# Schematic.net
KiCad netlist of a schematic drawn in EAGLE
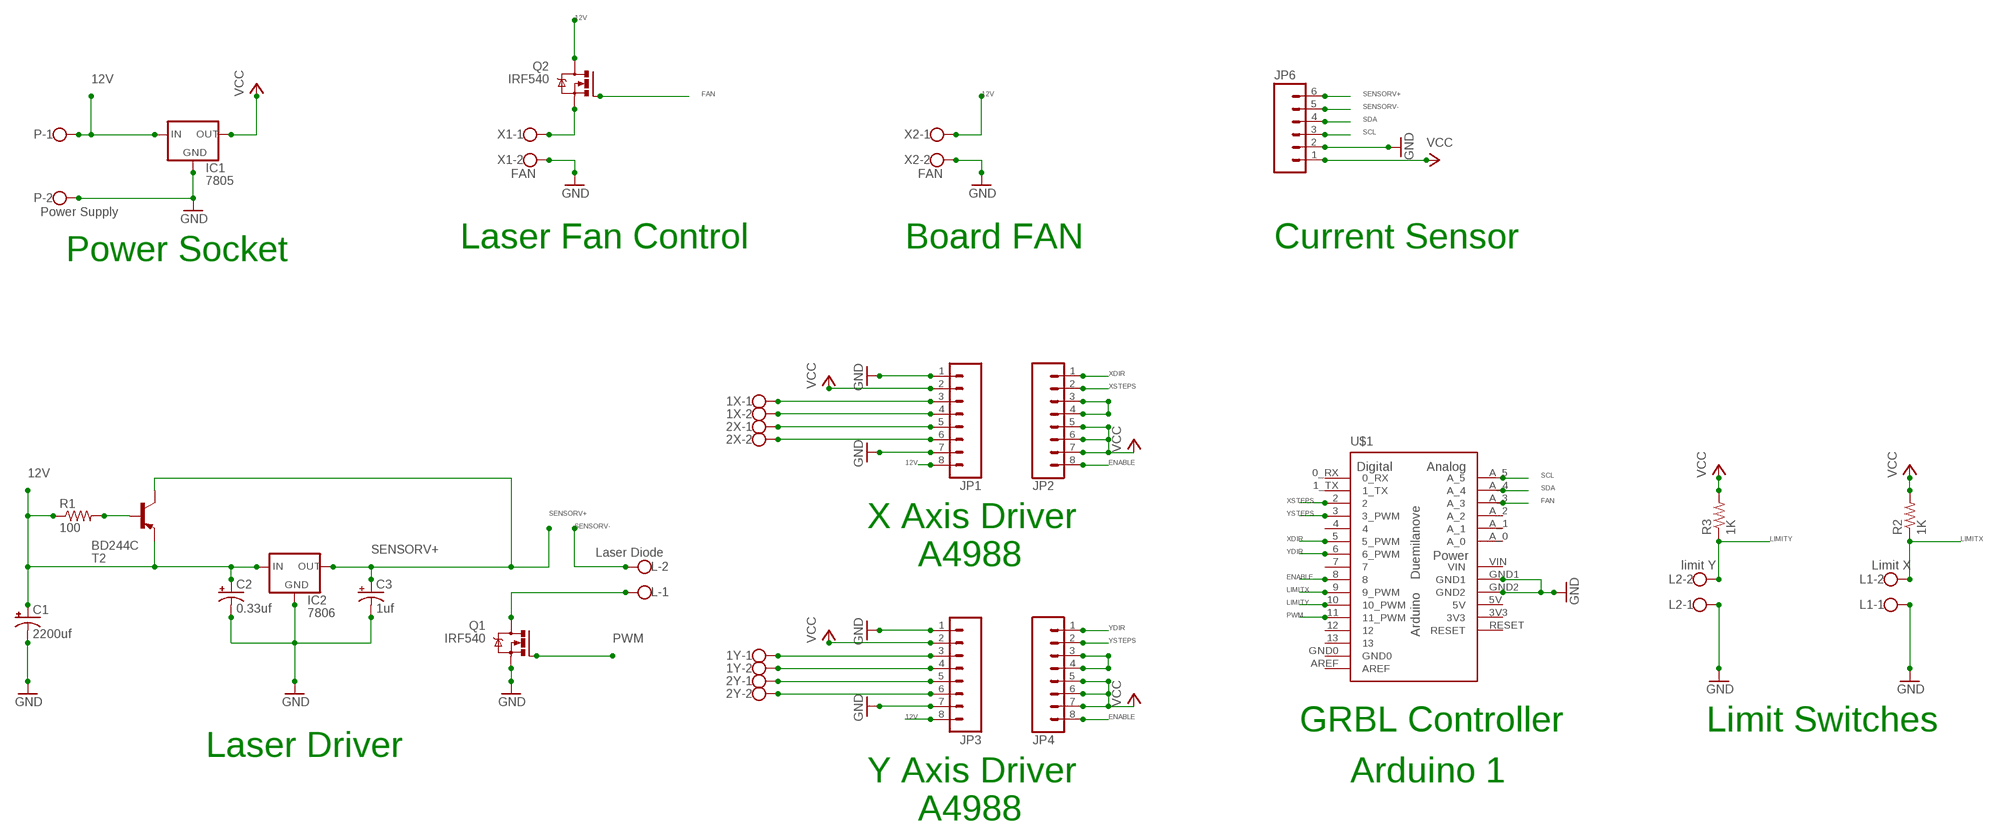
[diagram p0: schematic, sheet 1]

(export (version "E")
  (design (tool "Eeschema 10.0.6"))
  (components
    (comp (ref "1X")
      (value "W237-102")
      (footprint "eagle-import:W237-102")
      (fields (field (name "MPN") "237-102"))
      (libsource (lib "eagle-import") (part "W237-102"))
    )
    (comp (ref "1Y")
      (value "W237-102")
      (footprint "eagle-import:W237-102")
      (fields (field (name "MPN") "237-102"))
      (libsource (lib "eagle-import") (part "W237-102"))
    )
    (comp (ref "2X")
      (value "W237-102")
      (footprint "eagle-import:W237-102")
      (fields (field (name "MPN") "237-102"))
      (libsource (lib "eagle-import") (part "W237-102"))
    )
    (comp (ref "2Y")
      (value "W237-102")
      (footprint "eagle-import:W237-102")
      (fields (field (name "MPN") "237-102"))
      (libsource (lib "eagle-import") (part "W237-102"))
    )
    (comp (ref "C1")
      (value "2200uf")
      (footprint "eagle-import:CPOL-RADIAL-1000UF-25V")
      (libsource (lib "eagle-import") (part "CAP_POLPTH4"))
    )
    (comp (ref "C2")
      (value "0.33uf")
      (footprint "eagle-import:CPOL-RADIAL-10UF-25V")
      (libsource (lib "eagle-import") (part "CAP_POLPTH2"))
    )
    (comp (ref "C3")
      (value "1uf")
      (footprint "eagle-import:CPOL-RADIAL-10UF-25V")
      (libsource (lib "eagle-import") (part "CAP_POLPTH2"))
    )
    (comp (ref "IC1")
      (value "7805")
      (footprint "eagle-import:TO220-IGO")
      (libsource (lib "eagle-import") (part "V_REG_78XXSINK"))
    )
    (comp (ref "IC2")
      (value "7806")
      (footprint "eagle-import:TO220-IGO")
      (libsource (lib "eagle-import") (part "V_REG_78XXSINK"))
    )
    (comp (ref "JP1")
      (value "M08")
      (footprint "eagle-import:1X08")
      (libsource (lib "eagle-import") (part "M08"))
    )
    (comp (ref "JP2")
      (value "M08")
      (footprint "eagle-import:1X08")
      (libsource (lib "eagle-import") (part "M08"))
    )
    (comp (ref "JP3")
      (value "M08")
      (footprint "eagle-import:1X08")
      (libsource (lib "eagle-import") (part "M08"))
    )
    (comp (ref "JP4")
      (value "M08")
      (footprint "eagle-import:1X08")
      (libsource (lib "eagle-import") (part "M08"))
    )
    (comp (ref "JP6")
      (value "M06LONGPADS")
      (footprint "eagle-import:1X06_LONGPADS")
      (libsource (lib "eagle-import") (part "M06LONGPADS"))
    )
    (comp (ref "L")
      (value "Laser Diode")
      (footprint "eagle-import:W237-102")
      (fields (field (name "MPN") "237-102"))
      (libsource (lib "eagle-import") (part "W237-102"))
    )
    (comp (ref "L1")
      (value "Limit X")
      (footprint "eagle-import:W237-102")
      (fields (field (name "MPN") "237-102"))
      (libsource (lib "eagle-import") (part "W237-102"))
    )
    (comp (ref "L2")
      (value "limit Y")
      (footprint "eagle-import:W237-102")
      (fields (field (name "MPN") "237-102"))
      (libsource (lib "eagle-import") (part "W237-102"))
    )
    (comp (ref "P")
      (value "Power Supply")
      (footprint "eagle-import:W237-102")
      (fields (field (name "MPN") "237-102"))
      (libsource (lib "eagle-import") (part "W237-102"))
    )
    (comp (ref "Q1")
      (value "IRF540")
      (footprint "eagle-import:TO220BV")
      (libsource (lib "eagle-import") (part "IRF540"))
    )
    (comp (ref "Q2")
      (value "IRF540")
      (footprint "eagle-import:TO220BV")
      (libsource (lib "eagle-import") (part "IRF540"))
    )
    (comp (ref "R1")
      (value "100")
      (footprint "eagle-import:1_6W-RES")
      (libsource (lib "eagle-import") (part "RESISTORPTH-1/6W"))
    )
    (comp (ref "R2")
      (value "1K")
      (footprint "eagle-import:1_6W-RES")
      (libsource (lib "eagle-import") (part "RESISTORPTH-1/6W"))
    )
    (comp (ref "R3")
      (value "1K")
      (footprint "eagle-import:1_6W-RES")
      (libsource (lib "eagle-import") (part "RESISTORPTH-1/6W"))
    )
    (comp (ref "T2")
      (value "BD244C")
      (footprint "eagle-import:TO220V")
      (libsource (lib "eagle-import") (part "-PNP-TO220V"))
    )
    (comp (ref "U$1")
      (value "ARDUINO-USBLONG_PADS_TEXT")
      (footprint "eagle-import:SHIELD")
      (libsource (lib "eagle-import") (part "ARDUINO-USBLONG_PADS_TEXT"))
    )
    (comp (ref "X1")
      (value "FAN")
      (footprint "eagle-import:W237-102")
      (fields (field (name "MPN") "237-102"))
      (libsource (lib "eagle-import") (part "W237-102"))
    )
    (comp (ref "X2")
      (value "FAN")
      (footprint "eagle-import:W237-102")
      (fields (field (name "MPN") "237-102"))
      (libsource (lib "eagle-import") (part "W237-102"))
    )
  )
  (nets
    (net (code "1") (name "/3V3") (class "Default")
      (node (ref "U$1") (pin "3V3") (pinfunction "3V3_3V3") (pintype "power_in"))
    )
    (net (code "2") (name "/5V") (class "Default")
      (node (ref "U$1") (pin "5V") (pinfunction "5V_5V") (pintype "power_in"))
    )
    (net (code "3") (name "/12V") (class "Default")
      (node (ref "C1") (pin "1") (pinfunction "+_1") (pintype "passive"))
      (node (ref "C2") (pin "1") (pinfunction "+_1") (pintype "passive"))
      (node (ref "IC1") (pin "IN") (pinfunction "IN_IN") (pintype "input"))
      (node (ref "IC2") (pin "IN") (pinfunction "IN_IN") (pintype "input"))
      (node (ref "JP1") (pin "8") (pinfunction "8_8") (pintype "passive"))
      (node (ref "JP3") (pin "8") (pinfunction "8_8") (pintype "passive"))
      (node (ref "P") (pin "1") (pinfunction "KL_1") (pintype "passive"))
      (node (ref "Q2") (pin "D") (pinfunction "D_D") (pintype "passive"))
      (node (ref "R1") (pin "1") (pinfunction "1_1") (pintype "passive"))
      (node (ref "T2") (pin "3") (pinfunction "E_3") (pintype "passive"))
      (node (ref "X2") (pin "1") (pinfunction "KL_1") (pintype "passive"))
    )
    (net (code "4") (name "/ENABLE") (class "Default")
      (node (ref "JP2") (pin "8") (pinfunction "8_8") (pintype "passive"))
      (node (ref "JP4") (pin "8") (pinfunction "8_8") (pintype "passive"))
      (node (ref "U$1") (pin "8") (pinfunction "8_8") (pintype "bidirectional"))
    )
    (net (code "5") (name "/FAN") (class "Default")
      (node (ref "Q2") (pin "G") (pinfunction "G_G") (pintype "passive"))
      (node (ref "U$1") (pin "A_3") (pinfunction "A_3_A_3") (pintype "input"))
    )
    (net (code "6") (name "/GND0") (class "Default")
      (node (ref "U$1") (pin "GND0") (pinfunction "GND0_GND0") (pintype "power_in"))
    )
    (net (code "7") (name "/LIMITX") (class "Default")
      (node (ref "L1") (pin "2") (pinfunction "KL_2") (pintype "passive"))
      (node (ref "R2") (pin "1") (pinfunction "1_1") (pintype "passive"))
      (node (ref "U$1") (pin "9") (pinfunction "9_PWM_9") (pintype "bidirectional"))
    )
    (net (code "8") (name "/LIMITY") (class "Default")
      (node (ref "L2") (pin "2") (pinfunction "KL_2") (pintype "passive"))
      (node (ref "R3") (pin "1") (pinfunction "1_1") (pintype "passive"))
      (node (ref "U$1") (pin "10") (pinfunction "10_PWM_10") (pintype "bidirectional"))
    )
    (net (code "9") (name "/PWM") (class "Default")
      (node (ref "Q1") (pin "G") (pinfunction "G_G") (pintype "passive"))
      (node (ref "U$1") (pin "11") (pinfunction "11_PWM_11") (pintype "bidirectional"))
    )
    (net (code "10") (name "/SCL") (class "Default")
      (node (ref "JP6") (pin "3") (pinfunction "3_3") (pintype "passive"))
      (node (ref "U$1") (pin "A_5") (pinfunction "A_5_A_5") (pintype "input"))
    )
    (net (code "11") (name "/SDA") (class "Default")
      (node (ref "JP6") (pin "4") (pinfunction "4_4") (pintype "passive"))
      (node (ref "U$1") (pin "A_4") (pinfunction "A_4_A_4") (pintype "input"))
    )
    (net (code "12") (name "/SENSORV+") (class "Default")
      (node (ref "C3") (pin "1") (pinfunction "+_1") (pintype "passive"))
      (node (ref "IC2") (pin "OUT") (pinfunction "OUT_OUT") (pintype "output"))
      (node (ref "JP6") (pin "6") (pinfunction "6_6") (pintype "passive"))
      (node (ref "T2") (pin "2") (pinfunction "C_2") (pintype "passive"))
    )
    (net (code "13") (name "/SENSORV-") (class "Default")
      (node (ref "JP6") (pin "5") (pinfunction "5_5") (pintype "passive"))
      (node (ref "L") (pin "2") (pinfunction "KL_2") (pintype "passive"))
    )
    (net (code "14") (name "/VIN") (class "Default")
      (node (ref "U$1") (pin "VIN") (pinfunction "VIN_VIN") (pintype "power_in"))
    )
    (net (code "15") (name "/XDIR") (class "Default")
      (node (ref "JP2") (pin "1") (pinfunction "1_1") (pintype "passive"))
      (node (ref "U$1") (pin "5") (pinfunction "5_PWM_5") (pintype "bidirectional"))
    )
    (net (code "16") (name "/XSTEPS") (class "Default")
      (node (ref "JP2") (pin "2") (pinfunction "2_2") (pintype "passive"))
      (node (ref "U$1") (pin "2") (pinfunction "2_2") (pintype "bidirectional"))
    )
    (net (code "17") (name "/YDIR") (class "Default")
      (node (ref "JP4") (pin "1") (pinfunction "1_1") (pintype "passive"))
      (node (ref "U$1") (pin "6") (pinfunction "6_PWM_6") (pintype "bidirectional"))
    )
    (net (code "18") (name "/YSTEPS") (class "Default")
      (node (ref "JP4") (pin "2") (pinfunction "2_2") (pintype "passive"))
      (node (ref "U$1") (pin "3") (pinfunction "3_PWM_3") (pintype "bidirectional"))
    )
    (net (code "19") (name "GND") (class "Default")
      (node (ref "C1") (pin "2") (pinfunction "-_2") (pintype "passive"))
      (node (ref "C2") (pin "2") (pinfunction "-_2") (pintype "passive"))
      (node (ref "C3") (pin "2") (pinfunction "-_2") (pintype "passive"))
      (node (ref "IC1") (pin "GND") (pinfunction "GND_GND") (pintype "input"))
      (node (ref "IC2") (pin "GND") (pinfunction "GND_GND") (pintype "input"))
      (node (ref "JP1") (pin "1") (pinfunction "1_1") (pintype "passive"))
      (node (ref "JP1") (pin "7") (pinfunction "7_7") (pintype "passive"))
      (node (ref "JP3") (pin "1") (pinfunction "1_1") (pintype "passive"))
      (node (ref "JP3") (pin "7") (pinfunction "7_7") (pintype "passive"))
      (node (ref "JP6") (pin "2") (pinfunction "2_2") (pintype "passive"))
      (node (ref "L1") (pin "1") (pinfunction "KL_1") (pintype "passive"))
      (node (ref "L2") (pin "1") (pinfunction "KL_1") (pintype "passive"))
      (node (ref "P") (pin "2") (pinfunction "KL_2") (pintype "passive"))
      (node (ref "Q1") (pin "S") (pinfunction "S_S") (pintype "passive"))
      (node (ref "U$1") (pin "GND1") (pinfunction "GND1_GND1") (pintype "power_in"))
      (node (ref "U$1") (pin "GND2") (pinfunction "GND2_GND2") (pintype "power_in"))
      (node (ref "X1") (pin "2") (pinfunction "KL_2") (pintype "passive"))
      (node (ref "X2") (pin "2") (pinfunction "KL_2") (pintype "passive"))
    )
    (net (code "20") (name "Net-(1XA-KL)") (class "Default")
      (node (ref "1X") (pin "1") (pinfunction "KL_1") (pintype "passive"))
      (node (ref "JP1") (pin "3") (pinfunction "3_3") (pintype "passive"))
    )
    (net (code "21") (name "Net-(1XB-KL)") (class "Default")
      (node (ref "1X") (pin "2") (pinfunction "KL_2") (pintype "passive"))
      (node (ref "JP1") (pin "4") (pinfunction "4_4") (pintype "passive"))
    )
    (net (code "22") (name "Net-(1YA-KL)") (class "Default")
      (node (ref "1Y") (pin "1") (pinfunction "KL_1") (pintype "passive"))
      (node (ref "JP3") (pin "3") (pinfunction "3_3") (pintype "passive"))
    )
    (net (code "23") (name "Net-(1YB-KL)") (class "Default")
      (node (ref "1Y") (pin "2") (pinfunction "KL_2") (pintype "passive"))
      (node (ref "JP3") (pin "4") (pinfunction "4_4") (pintype "passive"))
    )
    (net (code "24") (name "Net-(2XA-KL)") (class "Default")
      (node (ref "2X") (pin "1") (pinfunction "KL_1") (pintype "passive"))
      (node (ref "JP1") (pin "5") (pinfunction "5_5") (pintype "passive"))
    )
    (net (code "25") (name "Net-(2XB-KL)") (class "Default")
      (node (ref "2X") (pin "2") (pinfunction "KL_2") (pintype "passive"))
      (node (ref "JP1") (pin "6") (pinfunction "6_6") (pintype "passive"))
    )
    (net (code "26") (name "Net-(2YA-KL)") (class "Default")
      (node (ref "2Y") (pin "1") (pinfunction "KL_1") (pintype "passive"))
      (node (ref "JP3") (pin "5") (pinfunction "5_5") (pintype "passive"))
    )
    (net (code "27") (name "Net-(2YB-KL)") (class "Default")
      (node (ref "2Y") (pin "2") (pinfunction "KL_2") (pintype "passive"))
      (node (ref "JP3") (pin "6") (pinfunction "6_6") (pintype "passive"))
    )
    (net (code "28") (name "Net-(JP2-Pad3)") (class "Default")
      (node (ref "JP2") (pin "3") (pinfunction "3_3") (pintype "passive"))
      (node (ref "JP2") (pin "4") (pinfunction "4_4") (pintype "passive"))
    )
    (net (code "29") (name "Net-(JP4-Pad3)") (class "Default")
      (node (ref "JP4") (pin "3") (pinfunction "3_3") (pintype "passive"))
      (node (ref "JP4") (pin "4") (pinfunction "4_4") (pintype "passive"))
    )
    (net (code "30") (name "Net-(LA-KL)") (class "Default")
      (node (ref "L") (pin "1") (pinfunction "KL_1") (pintype "passive"))
      (node (ref "Q1") (pin "D") (pinfunction "D_D") (pintype "passive"))
    )
    (net (code "31") (name "Net-(T2-B)") (class "Default")
      (node (ref "R1") (pin "2") (pinfunction "2_2") (pintype "passive"))
      (node (ref "T2") (pin "1") (pinfunction "B_1") (pintype "passive"))
    )
    (net (code "32") (name "Net-(X1A-KL)") (class "Default")
      (node (ref "Q2") (pin "S") (pinfunction "S_S") (pintype "passive"))
      (node (ref "X1") (pin "1") (pinfunction "KL_1") (pintype "passive"))
    )
    (net (code "33") (name "VCC") (class "Default")
      (node (ref "IC1") (pin "OUT") (pinfunction "OUT_OUT") (pintype "output"))
      (node (ref "JP1") (pin "2") (pinfunction "2_2") (pintype "passive"))
      (node (ref "JP2") (pin "5") (pinfunction "5_5") (pintype "passive"))
      (node (ref "JP2") (pin "6") (pinfunction "6_6") (pintype "passive"))
      (node (ref "JP2") (pin "7") (pinfunction "7_7") (pintype "passive"))
      (node (ref "JP3") (pin "2") (pinfunction "2_2") (pintype "passive"))
      (node (ref "JP4") (pin "5") (pinfunction "5_5") (pintype "passive"))
      (node (ref "JP4") (pin "6") (pinfunction "6_6") (pintype "passive"))
      (node (ref "JP4") (pin "7") (pinfunction "7_7") (pintype "passive"))
      (node (ref "JP6") (pin "1") (pinfunction "1_1") (pintype "passive"))
      (node (ref "R2") (pin "2") (pinfunction "2_2") (pintype "passive"))
      (node (ref "R3") (pin "2") (pinfunction "2_2") (pintype "passive"))
    )
    (net (code "34") (name "unconnected-(U$1-Pad0_RX)") (class "Default")
      (node (ref "U$1") (pin "0_RX") (pinfunction "0_RX_0_RX") (pintype "bidirectional"))
    )
    (net (code "35") (name "unconnected-(U$1-Pad1_TX)") (class "Default")
      (node (ref "U$1") (pin "1_TX") (pinfunction "1_TX_1_TX") (pintype "bidirectional"))
    )
    (net (code "36") (name "unconnected-(U$1-Pad4)") (class "Default")
      (node (ref "U$1") (pin "4") (pinfunction "4_4") (pintype "bidirectional"))
    )
    (net (code "37") (name "unconnected-(U$1-Pad7)") (class "Default")
      (node (ref "U$1") (pin "7") (pinfunction "7_7") (pintype "bidirectional"))
    )
    (net (code "38") (name "unconnected-(U$1-Pad12)") (class "Default")
      (node (ref "U$1") (pin "12") (pinfunction "12_12") (pintype "bidirectional"))
    )
    (net (code "39") (name "unconnected-(U$1-Pad13)") (class "Default")
      (node (ref "U$1") (pin "13") (pinfunction "13_13") (pintype "bidirectional"))
    )
    (net (code "40") (name "unconnected-(U$1-PadAREF)") (class "Default")
      (node (ref "U$1") (pin "AREF") (pinfunction "AREF_AREF") (pintype "bidirectional"))
    )
    (net (code "41") (name "unconnected-(U$1-PadA_0)") (class "Default")
      (node (ref "U$1") (pin "A_0") (pinfunction "A_0_A_0") (pintype "input"))
    )
    (net (code "42") (name "unconnected-(U$1-PadA_1)") (class "Default")
      (node (ref "U$1") (pin "A_1") (pinfunction "A_1_A_1") (pintype "input"))
    )
    (net (code "43") (name "unconnected-(U$1-PadA_2)") (class "Default")
      (node (ref "U$1") (pin "A_2") (pinfunction "A_2_A_2") (pintype "input"))
    )
    (net (code "44") (name "unconnected-(U$1-PadRESET)") (class "Default")
      (node (ref "U$1") (pin "RESET") (pinfunction "RESET_RESET") (pintype "input"))
    )
  )
)
